# MTP_worp1.net
KiCad netlist of a schematic drawn in EAGLE
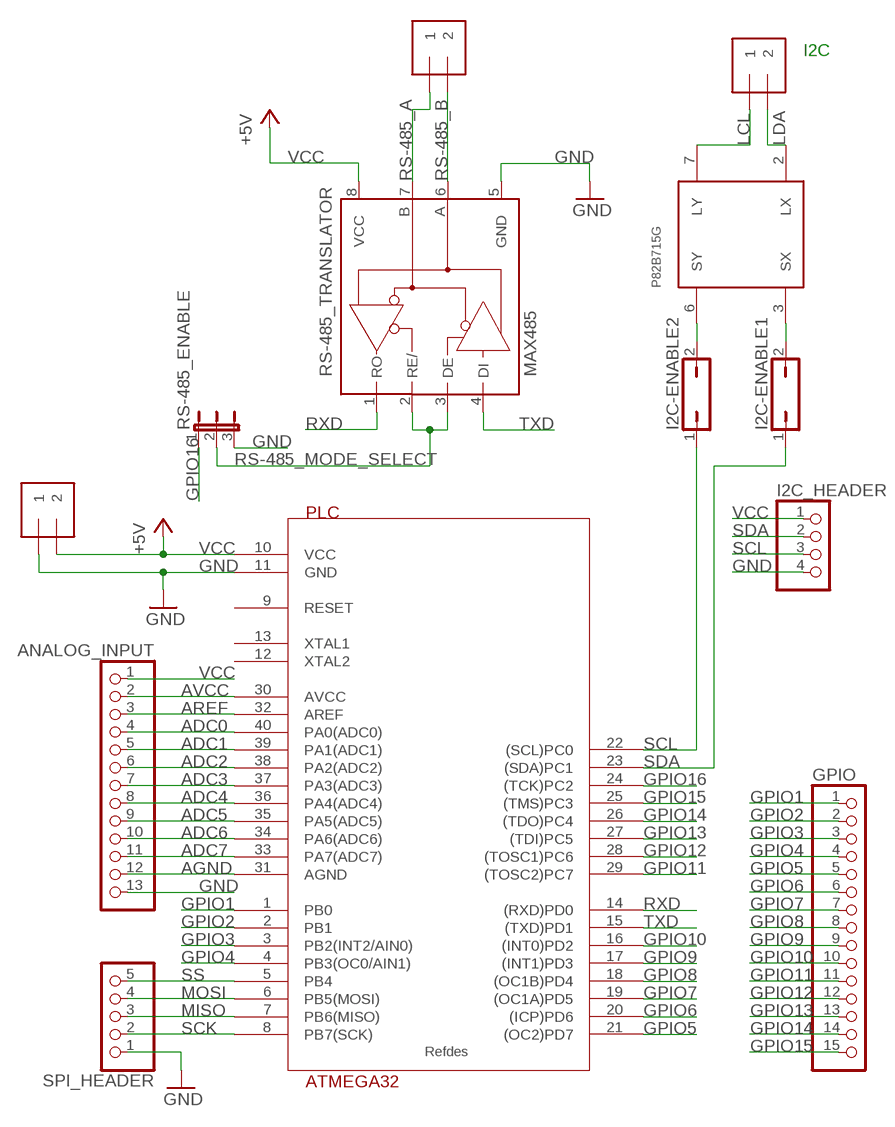
[diagram p0: schematic, sheet 1]

(export (version "E")
  (design (tool "Eeschema 10.0.6"))
  (components
    (comp (ref "ANALOG_INPUT")
      (value "PINHD-1X13")
      (footprint "eagle-import:1X13")
      (libsource (lib "eagle-import") (part "PINHD-1X13"))
    )
    (comp (ref "GPIO")
      (value "PINHD-1X15-CB")
      (footprint "eagle-import:1X15-CB")
      (libsource (lib "eagle-import") (part "PINHD-1X15-CB"))
    )
    (comp (ref "I2C")
      (value "1X2-3.5MM")
      (footprint "eagle-import:1X2-3.5MM")
      (libsource (lib "eagle-import") (part "1X2-3.5MM"))
    )
    (comp (ref "I2C-ENABLE1")
      (value "JP1Q")
      (footprint "eagle-import:JP1")
      (libsource (lib "eagle-import") (part "JP1Q"))
    )
    (comp (ref "I2C-ENABLE2")
      (value "JP1Q")
      (footprint "eagle-import:JP1")
      (libsource (lib "eagle-import") (part "JP1Q"))
    )
    (comp (ref "I2C_HEADER")
      (value "PINHD-1X4")
      (footprint "eagle-import:1X04")
      (libsource (lib "eagle-import") (part "PINHD-1X4"))
    )
    (comp (ref "P82B715")
      (value "82B715TD")
      (footprint "eagle-import:SO8")
      (fields (field (name "MPN") "P82B715TD,118"))
      (libsource (lib "eagle-import") (part "82B715TD"))
    )
    (comp (ref "PLC")
      (value "ATMEGA32")
      (footprint "eagle-import:DIP254P1524X482-40")
      (libsource (lib "eagle-import") (part "ATMEGA32-PU"))
    )
    (comp (ref "POWER")
      (value "1X2-3.5MM")
      (footprint "eagle-import:1X2-3.5MM")
      (libsource (lib "eagle-import") (part "1X2-3.5MM"))
    )
    (comp (ref "RS-485")
      (value "1X2-3.5MM")
      (footprint "eagle-import:1X2-3.5MM")
      (libsource (lib "eagle-import") (part "1X2-3.5MM"))
    )
    (comp (ref "RS-485_ENABLE")
      (value "JP2E")
      (footprint "eagle-import:JP2")
      (libsource (lib "eagle-import") (part "JP2E"))
    )
    (comp (ref "RS-485_TRANSLATOR")
      (value "MAX485")
      (footprint "eagle-import:DIL08")
      (libsource (lib "eagle-import") (part "MAX34PA68C"))
    )
    (comp (ref "SPI_HEADER")
      (value "PINHD-1X5")
      (footprint "eagle-import:1X05")
      (libsource (lib "eagle-import") (part "PINHD-1X5"))
    )
  )
  (nets
    (net (code "1") (name "+5V") (class "Default")
      (node (ref "ANALOG_INPUT") (pin "1") (pinfunction "1_1") (pintype "passive"))
      (node (ref "I2C_HEADER") (pin "1") (pinfunction "1_1") (pintype "passive"))
      (node (ref "PLC") (pin "10") (pinfunction "VCC_10") (pintype "power_in"))
      (node (ref "POWER") (pin "2") (pinfunction "2_2") (pintype "passive"))
      (node (ref "RS-485_TRANSLATOR") (pin "8") (pinfunction "VCC_8") (pintype "power_in"))
    )
    (net (code "2") (name "/ADC0") (class "Default")
      (node (ref "ANALOG_INPUT") (pin "4") (pinfunction "4_4") (pintype "passive"))
      (node (ref "PLC") (pin "40") (pinfunction "PA0(ADC0)_40") (pintype "bidirectional"))
    )
    (net (code "3") (name "/ADC1") (class "Default")
      (node (ref "ANALOG_INPUT") (pin "5") (pinfunction "5_5") (pintype "passive"))
      (node (ref "PLC") (pin "39") (pinfunction "PA1(ADC1)_39") (pintype "bidirectional"))
    )
    (net (code "4") (name "/ADC2") (class "Default")
      (node (ref "ANALOG_INPUT") (pin "6") (pinfunction "6_6") (pintype "passive"))
      (node (ref "PLC") (pin "38") (pinfunction "PA2(ADC2)_38") (pintype "bidirectional"))
    )
    (net (code "5") (name "/ADC3") (class "Default")
      (node (ref "ANALOG_INPUT") (pin "7") (pinfunction "7_7") (pintype "passive"))
      (node (ref "PLC") (pin "37") (pinfunction "PA3(ADC3)_37") (pintype "bidirectional"))
    )
    (net (code "6") (name "/ADC4") (class "Default")
      (node (ref "ANALOG_INPUT") (pin "8") (pinfunction "8_8") (pintype "passive"))
      (node (ref "PLC") (pin "36") (pinfunction "PA4(ADC4)_36") (pintype "bidirectional"))
    )
    (net (code "7") (name "/ADC5") (class "Default")
      (node (ref "ANALOG_INPUT") (pin "9") (pinfunction "9_9") (pintype "passive"))
      (node (ref "PLC") (pin "35") (pinfunction "PA5(ADC5)_35") (pintype "bidirectional"))
    )
    (net (code "8") (name "/ADC6") (class "Default")
      (node (ref "ANALOG_INPUT") (pin "10") (pinfunction "10_10") (pintype "passive"))
      (node (ref "PLC") (pin "34") (pinfunction "PA6(ADC6)_34") (pintype "bidirectional"))
    )
    (net (code "9") (name "/ADC7") (class "Default")
      (node (ref "ANALOG_INPUT") (pin "11") (pinfunction "11_11") (pintype "passive"))
      (node (ref "PLC") (pin "33") (pinfunction "PA7(ADC7)_33") (pintype "bidirectional"))
    )
    (net (code "10") (name "/AGND") (class "Default")
      (node (ref "ANALOG_INPUT") (pin "12") (pinfunction "12_12") (pintype "passive"))
      (node (ref "PLC") (pin "31") (pinfunction "AGND_31") (pintype "passive"))
    )
    (net (code "11") (name "/AREF") (class "Default")
      (node (ref "ANALOG_INPUT") (pin "3") (pinfunction "3_3") (pintype "passive"))
      (node (ref "PLC") (pin "32") (pinfunction "AREF_32") (pintype "input"))
    )
    (net (code "12") (name "/AVCC") (class "Default")
      (node (ref "ANALOG_INPUT") (pin "2") (pinfunction "2_2") (pintype "passive"))
      (node (ref "PLC") (pin "30") (pinfunction "AVCC_30") (pintype "power_in"))
    )
    (net (code "13") (name "/GPIO1") (class "Default")
      (node (ref "GPIO") (pin "1") (pinfunction "1_1") (pintype "passive"))
      (node (ref "PLC") (pin "1") (pinfunction "PB0_1") (pintype "bidirectional"))
    )
    (net (code "14") (name "/GPIO2") (class "Default")
      (node (ref "GPIO") (pin "2") (pinfunction "2_2") (pintype "passive"))
      (node (ref "PLC") (pin "2") (pinfunction "PB1_2") (pintype "bidirectional"))
    )
    (net (code "15") (name "/GPIO3") (class "Default")
      (node (ref "GPIO") (pin "3") (pinfunction "3_3") (pintype "passive"))
      (node (ref "PLC") (pin "3") (pinfunction "PB2(INT2/AIN0)_3") (pintype "bidirectional"))
    )
    (net (code "16") (name "/GPIO4") (class "Default")
      (node (ref "GPIO") (pin "4") (pinfunction "4_4") (pintype "passive"))
      (node (ref "PLC") (pin "4") (pinfunction "PB3(OC0/AIN1)_4") (pintype "bidirectional"))
    )
    (net (code "17") (name "/GPIO5") (class "Default")
      (node (ref "GPIO") (pin "5") (pinfunction "5_5") (pintype "passive"))
      (node (ref "PLC") (pin "21") (pinfunction "(OC2)PD7_21") (pintype "bidirectional"))
    )
    (net (code "18") (name "/GPIO6") (class "Default")
      (node (ref "GPIO") (pin "6") (pinfunction "6_6") (pintype "passive"))
      (node (ref "PLC") (pin "20") (pinfunction "(ICP)PD6_20") (pintype "bidirectional"))
    )
    (net (code "19") (name "/GPIO7") (class "Default")
      (node (ref "GPIO") (pin "7") (pinfunction "7_7") (pintype "passive"))
      (node (ref "PLC") (pin "19") (pinfunction "(OC1A)PD5_19") (pintype "bidirectional"))
    )
    (net (code "20") (name "/GPIO8") (class "Default")
      (node (ref "GPIO") (pin "8") (pinfunction "8_8") (pintype "passive"))
      (node (ref "PLC") (pin "18") (pinfunction "(OC1B)PD4_18") (pintype "bidirectional"))
    )
    (net (code "21") (name "/GPIO9") (class "Default")
      (node (ref "GPIO") (pin "9") (pinfunction "9_9") (pintype "passive"))
      (node (ref "PLC") (pin "17") (pinfunction "(INT1)PD3_17") (pintype "bidirectional"))
    )
    (net (code "22") (name "/GPIO10") (class "Default")
      (node (ref "GPIO") (pin "10") (pinfunction "10_10") (pintype "passive"))
      (node (ref "PLC") (pin "16") (pinfunction "(INT0)PD2_16") (pintype "bidirectional"))
    )
    (net (code "23") (name "/GPIO11") (class "Default")
      (node (ref "GPIO") (pin "11") (pinfunction "11_11") (pintype "passive"))
      (node (ref "PLC") (pin "29") (pinfunction "(TOSC2)PC7_29") (pintype "bidirectional"))
    )
    (net (code "24") (name "/GPIO12") (class "Default")
      (node (ref "GPIO") (pin "12") (pinfunction "12_12") (pintype "passive"))
      (node (ref "PLC") (pin "28") (pinfunction "(TOSC1)PC6_28") (pintype "bidirectional"))
    )
    (net (code "25") (name "/GPIO13") (class "Default")
      (node (ref "GPIO") (pin "13") (pinfunction "13_13") (pintype "passive"))
      (node (ref "PLC") (pin "27") (pinfunction "(TDI)PC5_27") (pintype "bidirectional"))
    )
    (net (code "26") (name "/GPIO14") (class "Default")
      (node (ref "GPIO") (pin "14") (pinfunction "14_14") (pintype "passive"))
      (node (ref "PLC") (pin "26") (pinfunction "(TDO)PC4_26") (pintype "bidirectional"))
    )
    (net (code "27") (name "/GPIO15") (class "Default")
      (node (ref "GPIO") (pin "15") (pinfunction "15_15") (pintype "passive"))
      (node (ref "PLC") (pin "25") (pinfunction "(TMS)PC3_25") (pintype "bidirectional"))
    )
    (net (code "28") (name "/GPIO16") (class "Default")
      (node (ref "PLC") (pin "24") (pinfunction "(TCK)PC2_24") (pintype "bidirectional"))
      (node (ref "RS-485_ENABLE") (pin "1") (pinfunction "1_1") (pintype "passive"))
    )
    (net (code "29") (name "/LCL") (class "Default")
      (node (ref "I2C") (pin "1") (pinfunction "1_1") (pintype "passive"))
      (node (ref "P82B715") (pin "7") (pinfunction "LY_7") (pintype "bidirectional"))
    )
    (net (code "30") (name "/LDA") (class "Default")
      (node (ref "I2C") (pin "2") (pinfunction "2_2") (pintype "passive"))
      (node (ref "P82B715") (pin "2") (pinfunction "LX_2") (pintype "bidirectional"))
    )
    (net (code "31") (name "/MISO") (class "Default")
      (node (ref "PLC") (pin "7") (pinfunction "PB6(MISO)_7") (pintype "bidirectional"))
      (node (ref "SPI_HEADER") (pin "3") (pinfunction "3_3") (pintype "passive"))
    )
    (net (code "32") (name "/MOSI") (class "Default")
      (node (ref "PLC") (pin "6") (pinfunction "PB5(MOSI)_6") (pintype "bidirectional"))
      (node (ref "SPI_HEADER") (pin "4") (pinfunction "4_4") (pintype "passive"))
    )
    (net (code "33") (name "/RS-485_A") (class "Default")
      (node (ref "RS-485") (pin "1") (pinfunction "1_1") (pintype "passive"))
      (node (ref "RS-485_TRANSLATOR") (pin "7") (pinfunction "B_7") (pintype "passive"))
    )
    (net (code "34") (name "/RS-485_B") (class "Default")
      (node (ref "RS-485") (pin "2") (pinfunction "2_2") (pintype "passive"))
      (node (ref "RS-485_TRANSLATOR") (pin "6") (pinfunction "A_6") (pintype "passive"))
    )
    (net (code "35") (name "/RS-485_MODE_SELECT") (class "Default")
      (node (ref "RS-485_ENABLE") (pin "2") (pinfunction "2_2") (pintype "passive"))
      (node (ref "RS-485_TRANSLATOR") (pin "2") (pinfunction "RE/_2") (pintype "input"))
      (node (ref "RS-485_TRANSLATOR") (pin "3") (pinfunction "DE_3") (pintype "input"))
    )
    (net (code "36") (name "/RXD") (class "Default")
      (node (ref "PLC") (pin "14") (pinfunction "(RXD)PD0_14") (pintype "bidirectional"))
      (node (ref "RS-485_TRANSLATOR") (pin "1") (pinfunction "RO_1") (pintype "output"))
    )
    (net (code "37") (name "/SCK") (class "Default")
      (node (ref "PLC") (pin "8") (pinfunction "PB7(SCK)_8") (pintype "bidirectional"))
      (node (ref "SPI_HEADER") (pin "2") (pinfunction "2_2") (pintype "passive"))
    )
    (net (code "38") (name "/SCL") (class "Default")
      (node (ref "I2C-ENABLE2") (pin "1") (pinfunction "1_1") (pintype "passive"))
      (node (ref "I2C_HEADER") (pin "3") (pinfunction "3_3") (pintype "passive"))
      (node (ref "PLC") (pin "22") (pinfunction "(SCL)PC0_22") (pintype "bidirectional"))
    )
    (net (code "39") (name "/SDA") (class "Default")
      (node (ref "I2C-ENABLE1") (pin "1") (pinfunction "1_1") (pintype "passive"))
      (node (ref "I2C_HEADER") (pin "2") (pinfunction "2_2") (pintype "passive"))
      (node (ref "PLC") (pin "23") (pinfunction "(SDA)PC1_23") (pintype "bidirectional"))
    )
    (net (code "40") (name "/SS") (class "Default")
      (node (ref "PLC") (pin "5") (pinfunction "PB4_5") (pintype "bidirectional"))
      (node (ref "SPI_HEADER") (pin "5") (pinfunction "5_5") (pintype "passive"))
    )
    (net (code "41") (name "/TXD") (class "Default")
      (node (ref "PLC") (pin "15") (pinfunction "(TXD)PD1_15") (pintype "bidirectional"))
      (node (ref "RS-485_TRANSLATOR") (pin "4") (pinfunction "DI_4") (pintype "input"))
    )
    (net (code "42") (name "GND") (class "Default")
      (node (ref "ANALOG_INPUT") (pin "13") (pinfunction "13_13") (pintype "passive"))
      (node (ref "I2C_HEADER") (pin "4") (pinfunction "4_4") (pintype "passive"))
      (node (ref "PLC") (pin "11") (pinfunction "GND_11") (pintype "passive"))
      (node (ref "POWER") (pin "1") (pinfunction "1_1") (pintype "passive"))
      (node (ref "RS-485_ENABLE") (pin "3") (pinfunction "3_3") (pintype "passive"))
      (node (ref "RS-485_TRANSLATOR") (pin "5") (pinfunction "GND_5") (pintype "power_in"))
      (node (ref "SPI_HEADER") (pin "1") (pinfunction "1_1") (pintype "passive"))
    )
    (net (code "43") (name "Net-(P82B715A-SX)") (class "Default")
      (node (ref "I2C-ENABLE1") (pin "2") (pinfunction "2_2") (pintype "passive"))
      (node (ref "P82B715") (pin "3") (pinfunction "SX_3") (pintype "bidirectional"))
    )
    (net (code "44") (name "Net-(P82B715A-SY)") (class "Default")
      (node (ref "I2C-ENABLE2") (pin "2") (pinfunction "2_2") (pintype "passive"))
      (node (ref "P82B715") (pin "6") (pinfunction "SY_6") (pintype "bidirectional"))
    )
    (net (code "45") (name "unconnected-(PLC-RESET-Pad9)") (class "Default")
      (node (ref "PLC") (pin "9") (pinfunction "RESET_9") (pintype "input"))
    )
    (net (code "46") (name "unconnected-(PLC-XTAL1-Pad13)") (class "Default")
      (node (ref "PLC") (pin "13") (pinfunction "XTAL1_13") (pintype "input"))
    )
    (net (code "47") (name "unconnected-(PLC-XTAL2-Pad12)") (class "Default")
      (node (ref "PLC") (pin "12") (pinfunction "XTAL2_12") (pintype "output"))
    )
  )
)
